# ProPrj_Joystick_2025-05-01.net
KiCad netlist of a schematic drawn in EasyEDA Pro
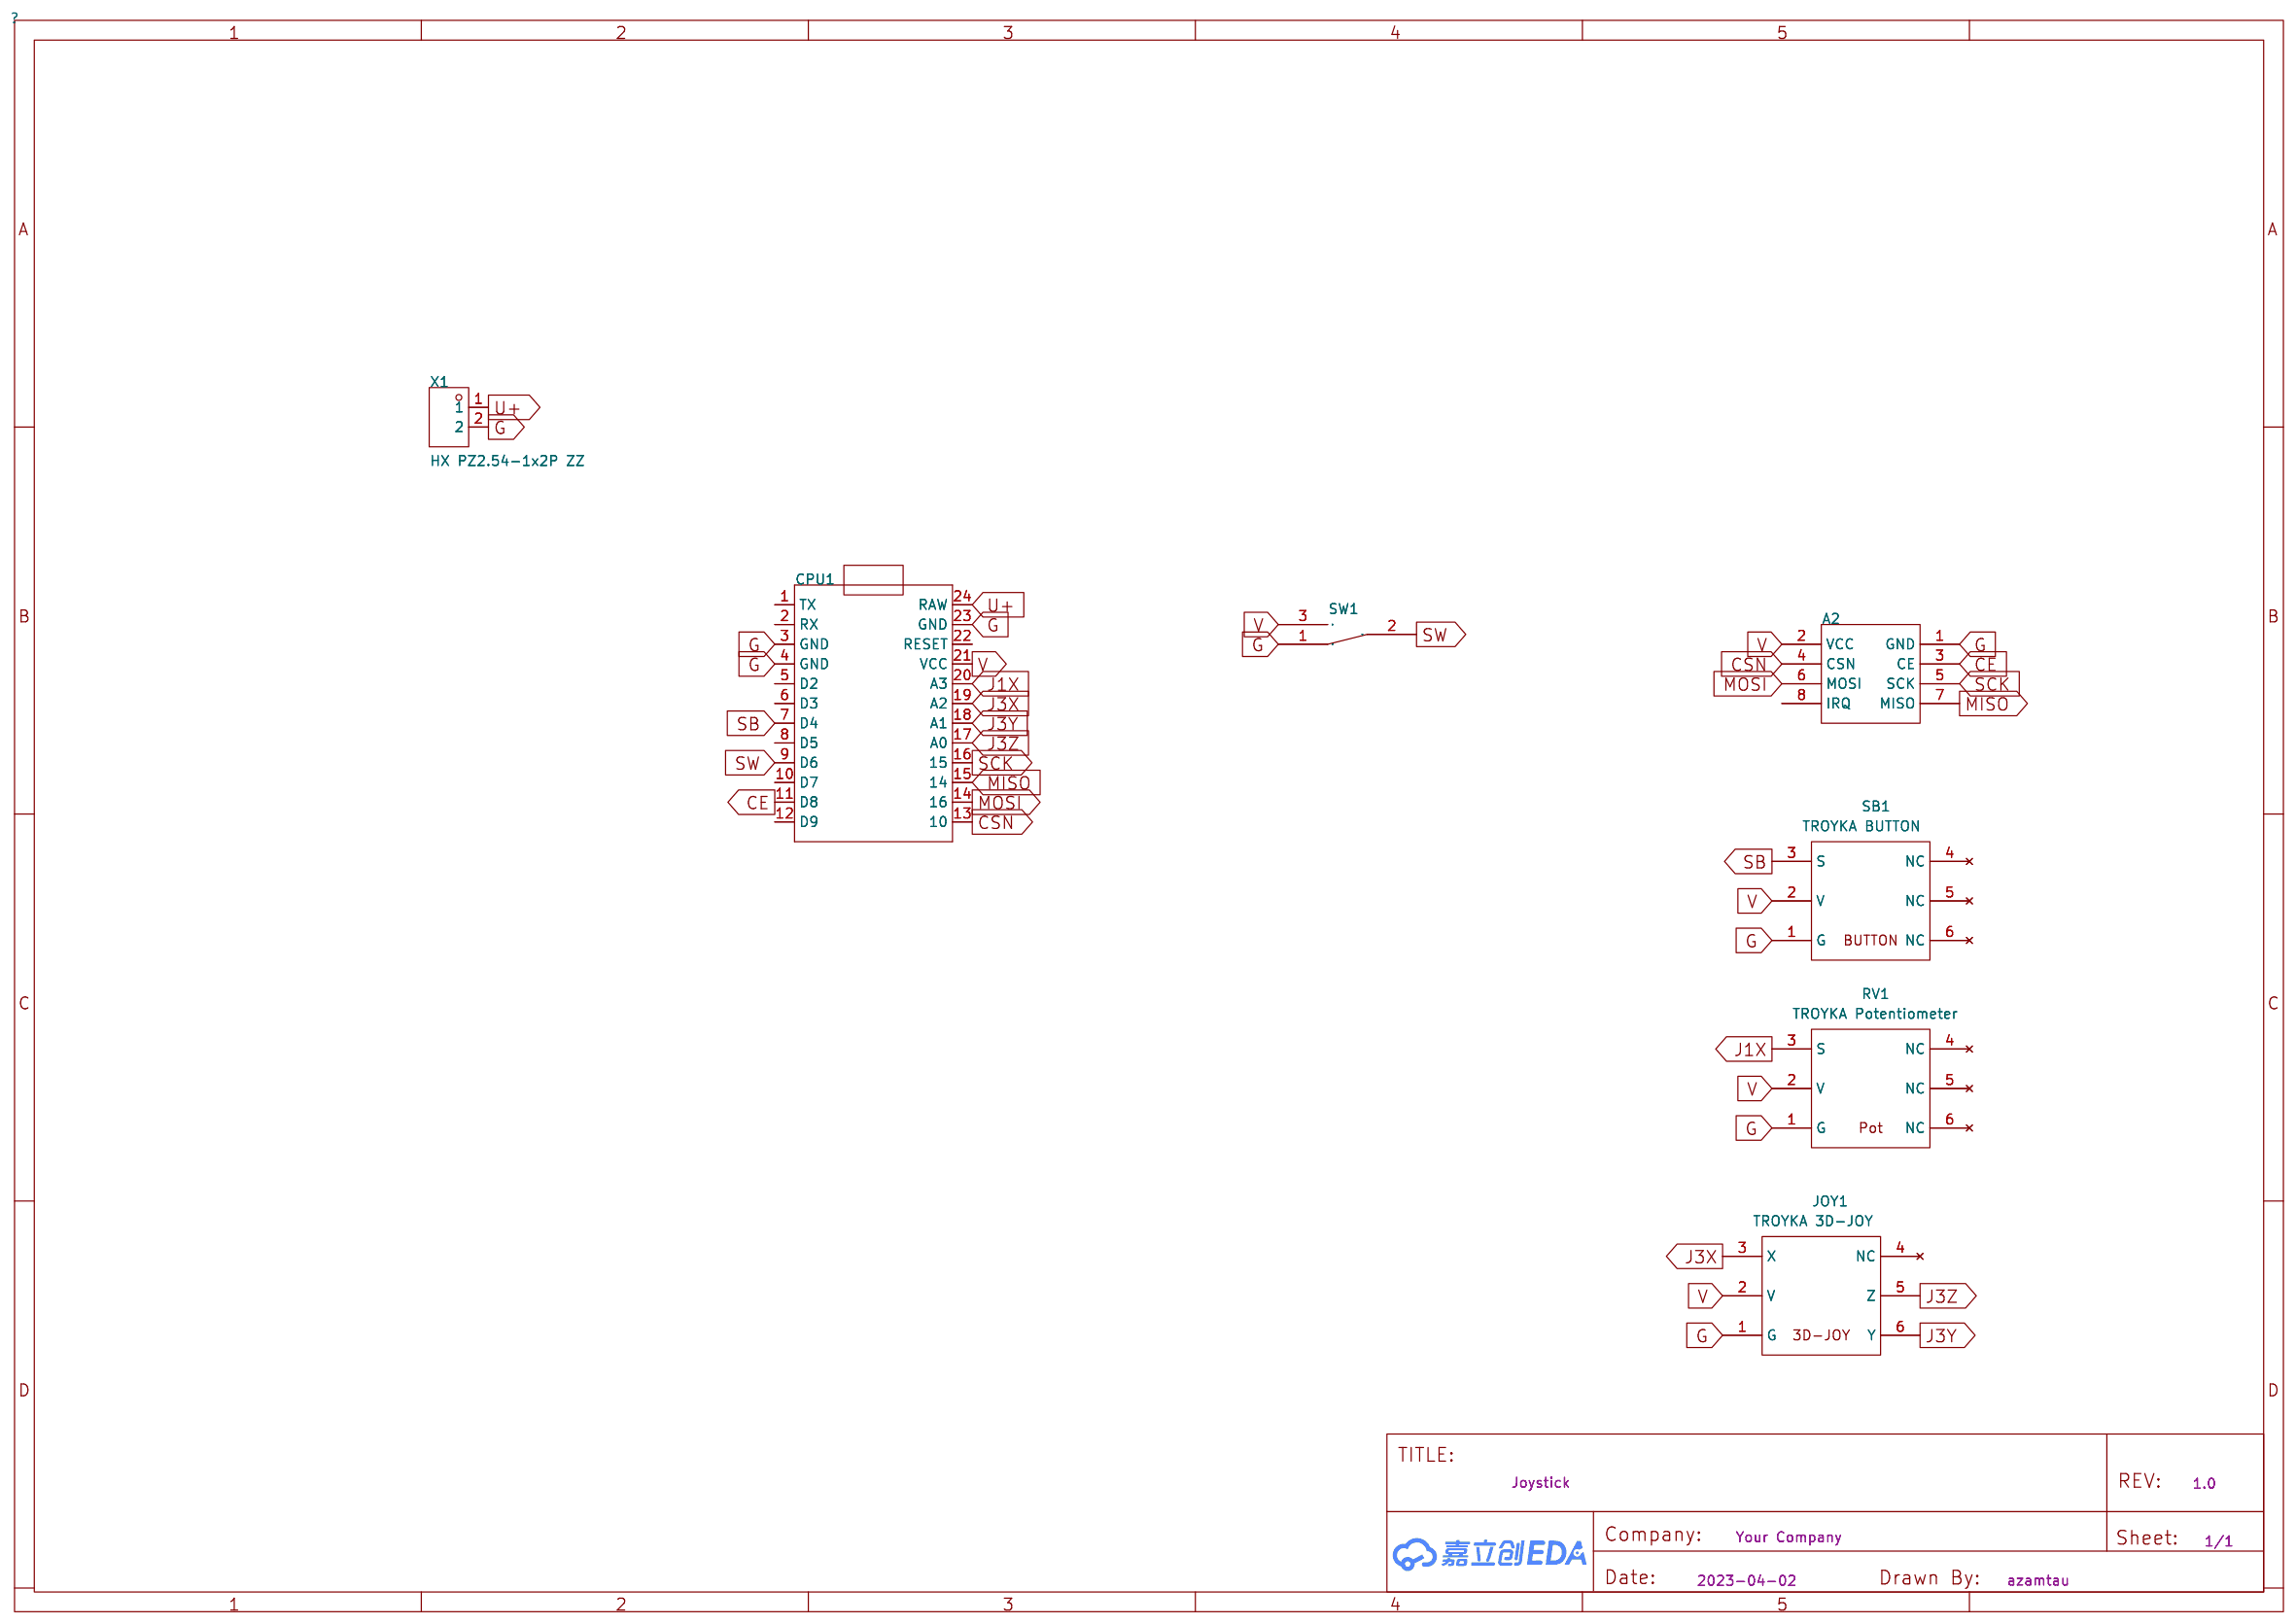
[diagram p0: schematic sheet]

(export (version "E")
  (design (tool "Eeschema 10.0.6"))
  (components
    (comp (ref "A2")
      (value "~")
      (footprint "easyedapro:MODULE, NRF24L01+")
      (libsource (lib "easyedapro") (part "MODULE, NRF24L01+"))
    )
    (comp (ref "CPU1")
      (value "~")
      (footprint "easyedapro:ARDUINOPROMICROUSB")
      (description "Arduino Pro Micro с Micro USB (ATmega32U4 5v)")
      (libsource (lib "easyedapro") (part "Arduino Pro Micro"))
    )
    (comp (ref "JOY1")
      (value "TROYKA 3D-JOY")
      (footprint "easyedapro:TROYKA 3D-JOY")
      (libsource (lib "easyedapro") (part "TROYKA 3D-JOY"))
    )
    (comp (ref "RV1")
      (value "TROYKA Potentiometer")
      (footprint "easyedapro:TROYKA Potentiometer")
      (libsource (lib "easyedapro") (part "TROYKA Potentiometer"))
    )
    (comp (ref "SB1")
      (value "TROYKA BUTTON")
      (footprint "easyedapro:TROYKA BUTTON")
      (libsource (lib "easyedapro") (part "TROYKA BUTTON"))
    )
    (comp (ref "SW1")
      (value "ST-0-102-A01-T000-LF")
      (footprint "easyedapro:SW-TH_3P-L8.3-W5.2-P2.54_ST-0-102-A01-T000")
      (fields (field (name "Manufacturer") "YUEN FUNG(源丰)"))
      (libsource (lib "easyedapro") (part "ST-0-102-A01-T000-LF+PJ"))
    )
    (comp (ref "X1")
      (value "HX PZ2.54-1x2P ZZ")
      (footprint "easyedapro:HDR-TH_2P-P2.54-V-M-3")
      (fields (field (name "Manufacturer") "hanxia(韩下)"))
      (libsource (lib "easyedapro") (part "HX PZ2.54-1X2P ZZ"))
    )
  )
  (nets
    (net (code "1") (name "CE") (class "Default")
      (node (ref "A2") (pin "3") (pinfunction "CE_3") (pintype "unspecified"))
      (node (ref "CPU1") (pin "11") (pinfunction "D8_11") (pintype "input"))
    )
    (net (code "2") (name "CSN") (class "Default")
      (node (ref "A2") (pin "4") (pinfunction "CSN_4") (pintype "unspecified"))
      (node (ref "CPU1") (pin "13") (pinfunction "10_13") (pintype "input"))
    )
    (net (code "3") (name "G") (class "Default")
      (node (ref "A2") (pin "1") (pinfunction "GND_1") (pintype "unspecified"))
      (node (ref "CPU1") (pin "23") (pinfunction "GND_23") (pintype "input"))
      (node (ref "CPU1") (pin "3") (pinfunction "GND_3") (pintype "input"))
      (node (ref "CPU1") (pin "4") (pinfunction "GND_4") (pintype "input"))
      (node (ref "JOY1") (pin "1") (pinfunction "G_1") (pintype "unspecified"))
      (node (ref "RV1") (pin "1") (pinfunction "G_1") (pintype "unspecified"))
      (node (ref "SB1") (pin "1") (pinfunction "G_1") (pintype "unspecified"))
      (node (ref "SW1") (pin "1") (pinfunction "1_1") (pintype "unspecified"))
      (node (ref "X1") (pin "2") (pinfunction "2_2") (pintype "unspecified"))
    )
    (net (code "4") (name "J1X") (class "Default")
      (node (ref "CPU1") (pin "20") (pinfunction "A3_20") (pintype "input"))
      (node (ref "RV1") (pin "3") (pinfunction "S_3") (pintype "unspecified"))
    )
    (net (code "5") (name "J3X") (class "Default")
      (node (ref "CPU1") (pin "19") (pinfunction "A2_19") (pintype "input"))
      (node (ref "JOY1") (pin "3") (pinfunction "X_3") (pintype "unspecified"))
    )
    (net (code "6") (name "J3Y") (class "Default")
      (node (ref "CPU1") (pin "18") (pinfunction "A1_18") (pintype "input"))
      (node (ref "JOY1") (pin "6") (pinfunction "Y_6") (pintype "unspecified"))
    )
    (net (code "7") (name "J3Z") (class "Default")
      (node (ref "CPU1") (pin "17") (pinfunction "A0_17") (pintype "input"))
      (node (ref "JOY1") (pin "5") (pinfunction "Z_5") (pintype "unspecified"))
    )
    (net (code "8") (name "MISO") (class "Default")
      (node (ref "A2") (pin "7") (pinfunction "MISO_7") (pintype "unspecified"))
      (node (ref "CPU1") (pin "15") (pinfunction "14_15") (pintype "input"))
    )
    (net (code "9") (name "MOSI") (class "Default")
      (node (ref "A2") (pin "6") (pinfunction "MOSI_6") (pintype "unspecified"))
      (node (ref "CPU1") (pin "14") (pinfunction "16_14") (pintype "input"))
    )
    (net (code "10") (name "SB") (class "Default")
      (node (ref "CPU1") (pin "7") (pinfunction "D4_7") (pintype "input"))
      (node (ref "SB1") (pin "3") (pinfunction "S_3") (pintype "unspecified"))
    )
    (net (code "11") (name "SCK") (class "Default")
      (node (ref "A2") (pin "5") (pinfunction "SCK_5") (pintype "unspecified"))
      (node (ref "CPU1") (pin "16") (pinfunction "15_16") (pintype "input"))
    )
    (net (code "12") (name "SW") (class "Default")
      (node (ref "CPU1") (pin "9") (pinfunction "D6_9") (pintype "input"))
      (node (ref "SW1") (pin "2") (pinfunction "2_2") (pintype "unspecified"))
    )
    (net (code "13") (name "U+") (class "Default")
      (node (ref "CPU1") (pin "24") (pinfunction "RAW_24") (pintype "input"))
      (node (ref "X1") (pin "1") (pinfunction "1_1") (pintype "unspecified"))
    )
    (net (code "14") (name "V") (class "Default")
      (node (ref "A2") (pin "2") (pinfunction "VCC_2") (pintype "unspecified"))
      (node (ref "CPU1") (pin "21") (pinfunction "VCC_21") (pintype "input"))
      (node (ref "JOY1") (pin "2") (pinfunction "V_2") (pintype "unspecified"))
      (node (ref "RV1") (pin "2") (pinfunction "V_2") (pintype "unspecified"))
      (node (ref "SB1") (pin "2") (pinfunction "V_2") (pintype "unspecified"))
      (node (ref "SW1") (pin "3") (pinfunction "3_3") (pintype "unspecified"))
    )
    (net (code "15") (name "unconnected-(A2-IRQ-Pad8)") (class "Default")
      (node (ref "A2") (pin "8") (pinfunction "IRQ_8") (pintype "unspecified"))
    )
    (net (code "16") (name "unconnected-(CPU1-D2-Pad5)") (class "Default")
      (node (ref "CPU1") (pin "5") (pinfunction "D2_5") (pintype "input"))
    )
    (net (code "17") (name "unconnected-(CPU1-D3-Pad6)") (class "Default")
      (node (ref "CPU1") (pin "6") (pinfunction "D3_6") (pintype "input"))
    )
    (net (code "18") (name "unconnected-(CPU1-D5-Pad8)") (class "Default")
      (node (ref "CPU1") (pin "8") (pinfunction "D5_8") (pintype "input"))
    )
    (net (code "19") (name "unconnected-(CPU1-D7-Pad10)") (class "Default")
      (node (ref "CPU1") (pin "10") (pinfunction "D7_10") (pintype "input"))
    )
    (net (code "20") (name "unconnected-(CPU1-D9-Pad12)") (class "Default")
      (node (ref "CPU1") (pin "12") (pinfunction "D9_12") (pintype "input"))
    )
    (net (code "21") (name "unconnected-(CPU1-RESET-Pad22)") (class "Default")
      (node (ref "CPU1") (pin "22") (pinfunction "RESET_22") (pintype "input"))
    )
    (net (code "22") (name "unconnected-(CPU1-RX-Pad2)") (class "Default")
      (node (ref "CPU1") (pin "2") (pinfunction "RX_2") (pintype "input"))
    )
    (net (code "23") (name "unconnected-(CPU1-TX-Pad1)") (class "Default")
      (node (ref "CPU1") (pin "1") (pinfunction "TX_1") (pintype "input"))
    )
    (net (code "24") (name "unconnected-(JOY1-NC-Pad4)") (class "Default")
      (node (ref "JOY1") (pin "4") (pinfunction "NC_4") (pintype "no_connect"))
    )
    (net (code "25") (name "unconnected-(RV1-NC-Pad4)") (class "Default")
      (node (ref "RV1") (pin "4") (pinfunction "NC_4") (pintype "no_connect"))
    )
    (net (code "26") (name "unconnected-(RV1-NC-Pad5)") (class "Default")
      (node (ref "RV1") (pin "5") (pinfunction "NC_5") (pintype "no_connect"))
    )
    (net (code "27") (name "unconnected-(RV1-NC-Pad6)") (class "Default")
      (node (ref "RV1") (pin "6") (pinfunction "NC_6") (pintype "no_connect"))
    )
    (net (code "28") (name "unconnected-(SB1-NC-Pad4)") (class "Default")
      (node (ref "SB1") (pin "4") (pinfunction "NC_4") (pintype "no_connect"))
    )
    (net (code "29") (name "unconnected-(SB1-NC-Pad5)") (class "Default")
      (node (ref "SB1") (pin "5") (pinfunction "NC_5") (pintype "no_connect"))
    )
    (net (code "30") (name "unconnected-(SB1-NC-Pad6)") (class "Default")
      (node (ref "SB1") (pin "6") (pinfunction "NC_6") (pintype "no_connect"))
    )
  )
)
